# 10-Protections_2_of_2.net
KiCad netlist of a schematic drawn in Altium Designer
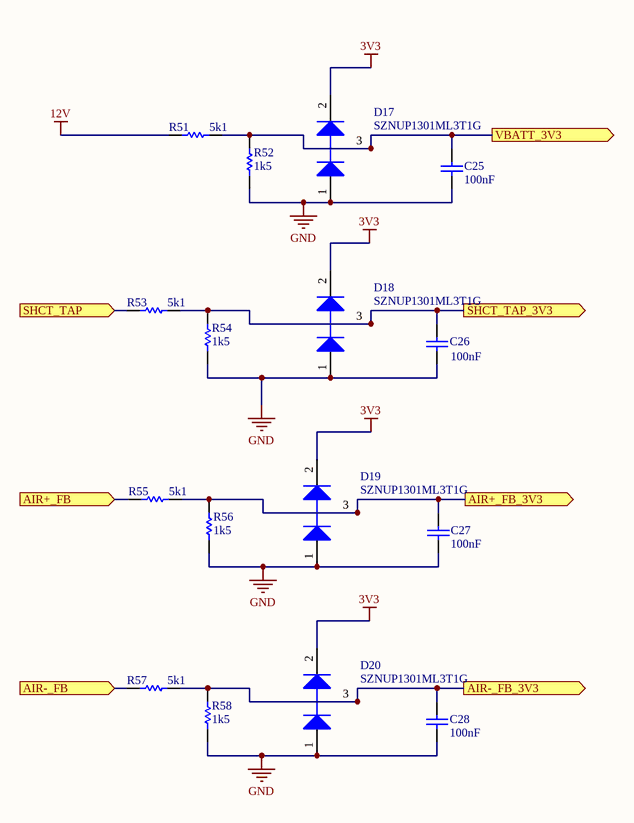
[diagram p0: 10-Protections 2 of 2.SchDoc]

(export (version "E")
  (design (tool "Eeschema 10.0.6"))
  (components
    (comp (ref "C25")
      (value "100nF")
      (footprint "1608[0603]")
      (description "Capacitor")
      (fields
        (field (name "MANUFACTURER") "Yageo")
        (field (name "MANUFACTURER PART NUMBER") "CC0603KRX7R9BB104")
      )
      (libsource (lib "Miscellaneous Devices") (part "Cap"))
    )
    (comp (ref "C26")
      (value "100nF")
      (footprint "1608[0603]")
      (description "Capacitor")
      (fields
        (field (name "MANUFACTURER") "Yageo")
        (field (name "MANUFACTURER PART NUMBER") "CC0603KRX7R9BB104")
      )
      (libsource (lib "Miscellaneous Devices") (part "Cap"))
    )
    (comp (ref "C27")
      (value "100nF")
      (footprint "1608[0603]")
      (description "Capacitor")
      (fields
        (field (name "MANUFACTURER") "Yageo")
        (field (name "MANUFACTURER PART NUMBER") "CC0603KRX7R9BB104")
      )
      (libsource (lib "Miscellaneous Devices") (part "Cap"))
    )
    (comp (ref "C28")
      (value "100nF")
      (footprint "1608[0603]")
      (description "Capacitor")
      (fields
        (field (name "MANUFACTURER") "Yageo")
        (field (name "MANUFACTURER PART NUMBER") "CC0603KRX7R9BB104")
      )
      (libsource (lib "Miscellaneous Devices") (part "Cap"))
    )
    (comp (ref "D17")
      (value "SZNUP1301ML3T1G")
      (footprint "ONSC-SOT-23-3-318-08_V")
      (fields (field (name "MANUFACTURER") "On Semiconductor"))
      (libsource (lib "Altium Content Vault") (part "ONSC-NUP1301-SOT-23-3-318-08"))
    )
    (comp (ref "D18")
      (value "SZNUP1301ML3T1G")
      (footprint "ONSC-SOT-23-3-318-08_V")
      (fields (field (name "MANUFACTURER") "On Semiconductor"))
      (libsource (lib "Altium Content Vault") (part "ONSC-NUP1301-SOT-23-3-318-08"))
    )
    (comp (ref "D19")
      (value "SZNUP1301ML3T1G")
      (footprint "ONSC-SOT-23-3-318-08_V")
      (fields (field (name "MANUFACTURER") "On Semiconductor"))
      (libsource (lib "Altium Content Vault") (part "ONSC-NUP1301-SOT-23-3-318-08"))
    )
    (comp (ref "D20")
      (value "SZNUP1301ML3T1G")
      (footprint "ONSC-SOT-23-3-318-08_V")
      (fields (field (name "MANUFACTURER") "On Semiconductor"))
      (libsource (lib "Altium Content Vault") (part "ONSC-NUP1301-SOT-23-3-318-08"))
    )
    (comp (ref "R51")
      (value "5k1")
      (footprint "1608[0603]")
      (description "Resistor")
      (fields
        (field (name "MANUFACTURER") "Yageo")
        (field (name "MANUFACTURER PART NUMBER") "RC0603JR-075K1L")
      )
      (libsource (lib "Miscellaneous Devices") (part "Res1"))
    )
    (comp (ref "R52")
      (value "1k5")
      (footprint "1608[0603]")
      (description "Resistor")
      (fields
        (field (name "MANUFACTURER") "Yageo")
        (field (name "MANUFACTURER PART NUMBER") "RC0603JR-075K1L")
      )
      (libsource (lib "Miscellaneous Devices") (part "Res1"))
    )
    (comp (ref "R53")
      (value "5k1")
      (footprint "1608[0603]")
      (description "Resistor")
      (fields
        (field (name "MANUFACTURER") "Yageo")
        (field (name "MANUFACTURER PART NUMBER") "RC0603JR-075K1L")
      )
      (libsource (lib "Miscellaneous Devices") (part "Res1"))
    )
    (comp (ref "R54")
      (value "1k5")
      (footprint "1608[0603]")
      (description "Resistor")
      (fields
        (field (name "MANUFACTURER") "Yageo")
        (field (name "MANUFACTURER PART NUMBER") "RC0603JR-075K1L")
      )
      (libsource (lib "Miscellaneous Devices") (part "Res1"))
    )
    (comp (ref "R55")
      (value "5k1")
      (footprint "1608[0603]")
      (description "Resistor")
      (fields
        (field (name "MANUFACTURER") "Yageo")
        (field (name "MANUFACTURER PART NUMBER") "RC0603JR-075K1L")
      )
      (libsource (lib "Miscellaneous Devices") (part "Res1"))
    )
    (comp (ref "R56")
      (value "1k5")
      (footprint "1608[0603]")
      (description "Resistor")
      (fields
        (field (name "MANUFACTURER") "Yageo")
        (field (name "MANUFACTURER PART NUMBER") "RC0603JR-075K1L")
      )
      (libsource (lib "Miscellaneous Devices") (part "Res1"))
    )
    (comp (ref "R57")
      (value "5k1")
      (footprint "1608[0603]")
      (description "Resistor")
      (fields
        (field (name "MANUFACTURER") "Yageo")
        (field (name "MANUFACTURER PART NUMBER") "RC0603JR-075K1L")
      )
      (libsource (lib "Miscellaneous Devices") (part "Res1"))
    )
    (comp (ref "R58")
      (value "1k5")
      (footprint "1608[0603]")
      (description "Resistor")
      (fields
        (field (name "MANUFACTURER") "Yageo")
        (field (name "MANUFACTURER PART NUMBER") "RC0603JR-075K1L")
      )
      (libsource (lib "Miscellaneous Devices") (part "Res1"))
    )
  )
  (nets
    (net (code "1") (name "/AIR+_FB") (class "Default")
      (node (ref "R55") (pin "1") (pinfunction "1_1") (pintype "passive"))
    )
    (net (code "2") (name "/AIR+_FB_3V3") (class "Default")
      (node (ref "C27") (pin "2") (pinfunction "2_2") (pintype "passive"))
      (node (ref "D19") (pin "3") (pinfunction "K/A_3") (pintype "passive"))
      (node (ref "R55") (pin "2") (pinfunction "2_2") (pintype "passive"))
      (node (ref "R56") (pin "2") (pinfunction "2_2") (pintype "passive"))
    )
    (net (code "3") (name "/AIR-_FB") (class "Default")
      (node (ref "R57") (pin "1") (pinfunction "1_1") (pintype "passive"))
    )
    (net (code "4") (name "/AIR-_FB_3V3") (class "Default")
      (node (ref "C28") (pin "2") (pinfunction "2_2") (pintype "passive"))
      (node (ref "D20") (pin "3") (pinfunction "K/A_3") (pintype "passive"))
      (node (ref "R57") (pin "2") (pinfunction "2_2") (pintype "passive"))
      (node (ref "R58") (pin "2") (pinfunction "2_2") (pintype "passive"))
    )
    (net (code "5") (name "/SHCT_TAP") (class "Default")
      (node (ref "R53") (pin "1") (pinfunction "1_1") (pintype "passive"))
    )
    (net (code "6") (name "/SHCT_TAP_3V3") (class "Default")
      (node (ref "C26") (pin "2") (pinfunction "2_2") (pintype "passive"))
      (node (ref "D18") (pin "3") (pinfunction "K/A_3") (pintype "passive"))
      (node (ref "R53") (pin "2") (pinfunction "2_2") (pintype "passive"))
      (node (ref "R54") (pin "2") (pinfunction "2_2") (pintype "passive"))
    )
    (net (code "7") (name "/VBATT_3V3") (class "Default")
      (node (ref "C25") (pin "2") (pinfunction "2_2") (pintype "passive"))
      (node (ref "D17") (pin "3") (pinfunction "K/A_3") (pintype "passive"))
      (node (ref "R51") (pin "2") (pinfunction "2_2") (pintype "passive"))
      (node (ref "R52") (pin "2") (pinfunction "2_2") (pintype "passive"))
    )
    (net (code "8") (name "3V3") (class "Default")
      (node (ref "D17") (pin "2") (pinfunction "K_2") (pintype "passive"))
      (node (ref "D18") (pin "2") (pinfunction "K_2") (pintype "passive"))
      (node (ref "D19") (pin "2") (pinfunction "K_2") (pintype "passive"))
      (node (ref "D20") (pin "2") (pinfunction "K_2") (pintype "passive"))
    )
    (net (code "9") (name "12V") (class "Default")
      (node (ref "R51") (pin "1") (pinfunction "1_1") (pintype "passive"))
    )
    (net (code "10") (name "GND") (class "Default")
      (node (ref "C25") (pin "1") (pinfunction "1_1") (pintype "passive"))
      (node (ref "C26") (pin "1") (pinfunction "1_1") (pintype "passive"))
      (node (ref "C27") (pin "1") (pinfunction "1_1") (pintype "passive"))
      (node (ref "C28") (pin "1") (pinfunction "1_1") (pintype "passive"))
      (node (ref "D17") (pin "1") (pinfunction "A_1") (pintype "passive"))
      (node (ref "D18") (pin "1") (pinfunction "A_1") (pintype "passive"))
      (node (ref "D19") (pin "1") (pinfunction "A_1") (pintype "passive"))
      (node (ref "D20") (pin "1") (pinfunction "A_1") (pintype "passive"))
      (node (ref "R52") (pin "1") (pinfunction "1_1") (pintype "passive"))
      (node (ref "R54") (pin "1") (pinfunction "1_1") (pintype "passive"))
      (node (ref "R56") (pin "1") (pinfunction "1_1") (pintype "passive"))
      (node (ref "R58") (pin "1") (pinfunction "1_1") (pintype "passive"))
    )
  )
)
